# ProPrj_sx1262_125cm_v0_2_2026-07-31.net
KiCad netlist of a schematic drawn in EasyEDA Pro
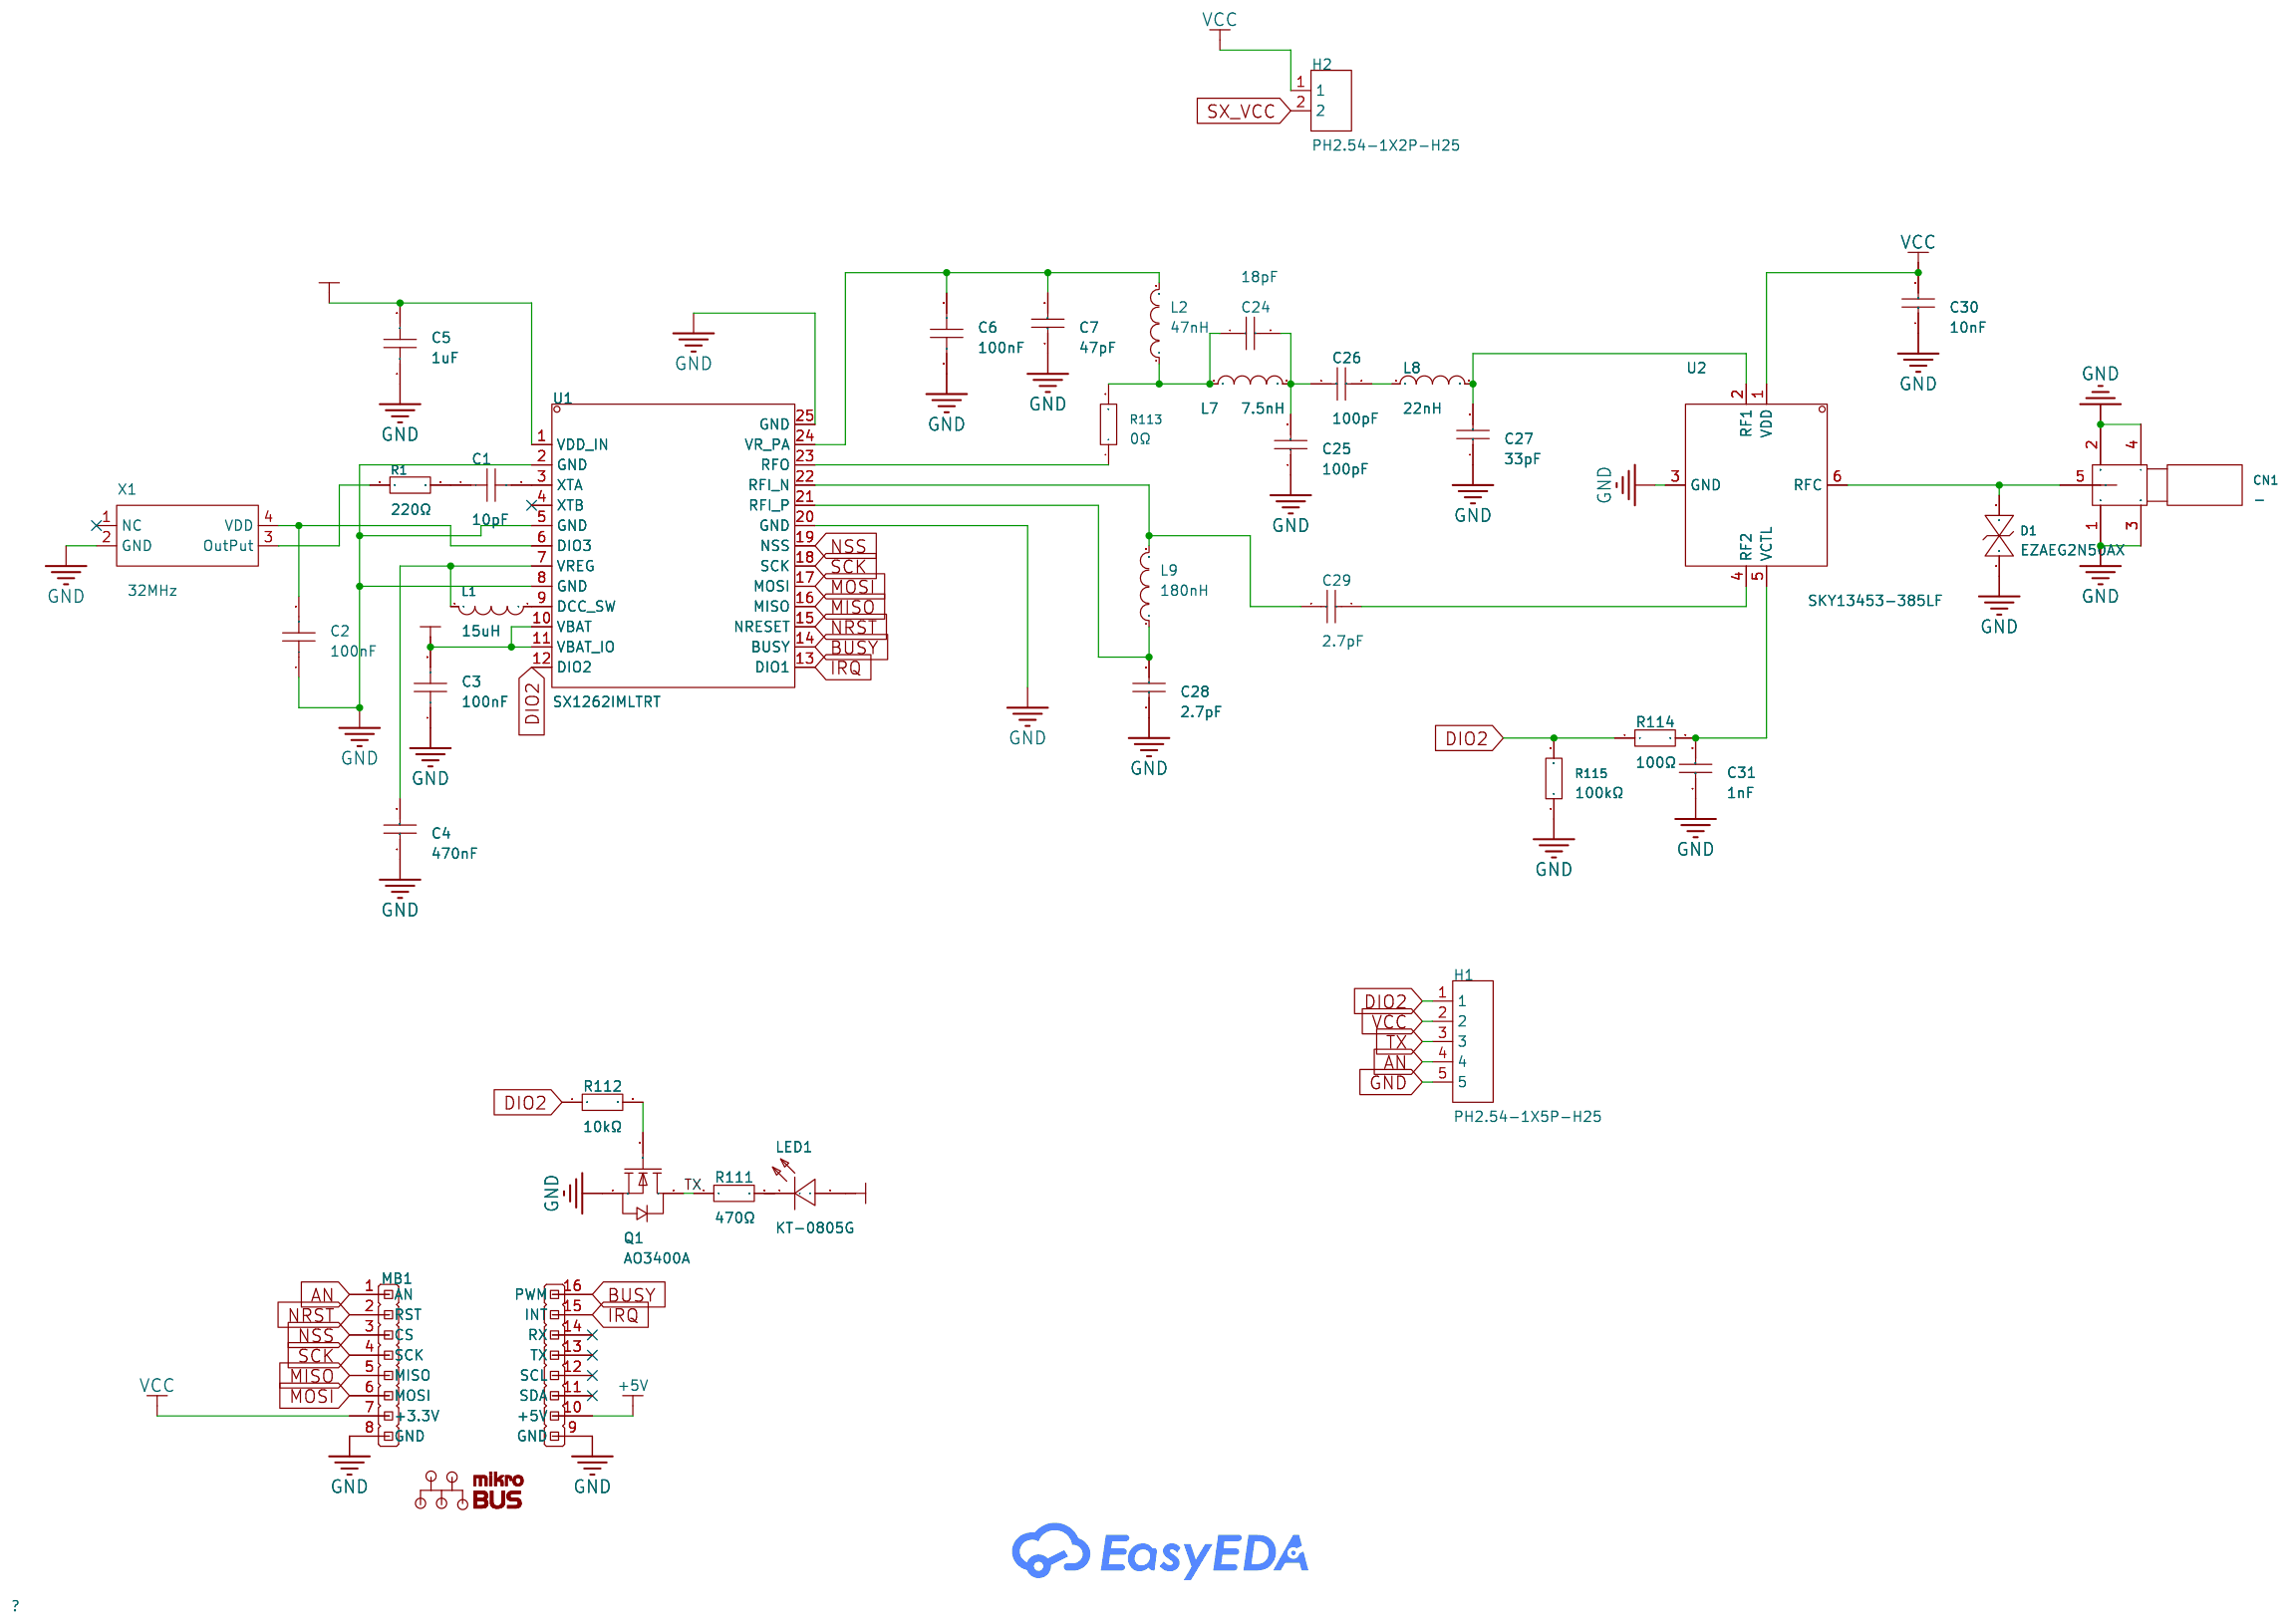
[diagram p0: schematic sheet]

(export (version "E")
  (design (tool "Eeschema 10.0.6"))
  (components
    (comp (ref "C1")
      (value "10pF")
      (footprint "easyedapro:C0402")
      (description "Capacitance:10pF Tolerance:±5% Tolerance:±5% Voltage Rating:50V Temperature Coefficient:C0G")
      (fields
        (field (name "Manufacturer Part") "CL05C100JB5NNNC")
        (field (name "Manufacturer") "SAMSUNG(三星)")
      )
      (libsource (lib "easyedapro") (part "CL05C100JB5NNNC"))
    )
    (comp (ref "C2")
      (value "100nF")
      (footprint "easyedapro:C0402")
      (description "Capacitance:100nF Tolerance:±10% Tolerance:±10% Voltage Rating:16V Temperature Coefficient:X7R")
      (fields
        (field (name "Manufacturer Part") "CL05B104KO5NNNC")
        (field (name "Manufacturer") "SAMSUNG(三星)")
      )
      (libsource (lib "easyedapro") (part "CL05B104KO5NNNC"))
    )
    (comp (ref "C3")
      (value "100nF")
      (footprint "easyedapro:C0402")
      (description "Capacitance:100nF Tolerance:±10% Tolerance:±10% Voltage Rating:16V Temperature Coefficient:X7R")
      (fields
        (field (name "Manufacturer Part") "CL05B104KO5NNNC")
        (field (name "Manufacturer") "SAMSUNG(三星)")
      )
      (libsource (lib "easyedapro") (part "CL05B104KO5NNNC"))
    )
    (comp (ref "C4")
      (value "470nF")
      (footprint "easyedapro:C0603")
      (description "Capacitance:470nF Tolerance:±10% Tolerance:±10% Voltage Rating:25V Temperature Coefficient:X7R")
      (fields
        (field (name "Manufacturer Part") "CL10B474KA8NNNC")
        (field (name "Manufacturer") "SAMSUNG(三星)")
      )
      (libsource (lib "easyedapro") (part "CL10B474KA8NNNC"))
    )
    (comp (ref "C5")
      (value "1uF")
      (footprint "easyedapro:C0402")
      (description "Capacitance:1uF Tolerance:±10% Tolerance:±10% Voltage Rating:25V Temperature Coefficient:X5R")
      (fields
        (field (name "Manufacturer Part") "CL05A105KA5NQNC")
        (field (name "Manufacturer") "SAMSUNG(三星)")
      )
      (libsource (lib "easyedapro") (part "CL05A105KA5NQNC"))
    )
    (comp (ref "C6")
      (value "100nF")
      (footprint "easyedapro:C0402")
      (description "Capacitance:100nF Tolerance:±10% Tolerance:±10% Voltage Rating:16V Temperature Coefficient:X7R")
      (fields
        (field (name "Manufacturer Part") "CL05B104KO5NNNC")
        (field (name "Manufacturer") "SAMSUNG(三星)")
      )
      (libsource (lib "easyedapro") (part "CL05B104KO5NNNC"))
    )
    (comp (ref "C7")
      (value "47pF")
      (footprint "easyedapro:C0402")
      (description "Capacitance:47pF Tolerance:±5% Tolerance:±5% Voltage Rating:50V Temperature Coefficient:C0G")
      (fields (field (name "Manufacturer Part") "0402CG470J500NT") (field (name "Manufacturer") "FH(风华)"))
      (libsource (lib "easyedapro") (part "0402CG470J500NT"))
    )
    (comp (ref "C24")
      (value "18pF")
      (footprint "easyedapro:C0402")
      (description "Capacitance:18pF Tolerance:±5% Tolerance:±5% Voltage Rating:50V Temperature Coefficient:C0G")
      (fields (field (name "Manufacturer Part") "0402CG180J500NT") (field (name "Manufacturer") "FH(风华)"))
      (libsource (lib "easyedapro") (part "0402CG330J500NT"))
    )
    (comp (ref "C25")
      (value "100pF")
      (footprint "easyedapro:C0402")
      (description "Capacitance:100pF Tolerance:±5% Tolerance:±5% Voltage Rating:50V Temperature Coefficient:C0G")
      (fields (field (name "Manufacturer Part") "0402CG101J500NT") (field (name "Manufacturer") "FH(风华)"))
      (libsource (lib "easyedapro") (part "GRM1555C1H8R2CA01D"))
    )
    (comp (ref "C26")
      (value "100pF")
      (footprint "easyedapro:C0402")
      (description "Capacitance:100pF Tolerance:±5% Tolerance:±5% Voltage Rating:50V Temperature Coefficient:C0G")
      (fields (field (name "Manufacturer Part") "0402CG101J500NT") (field (name "Manufacturer") "FH(风华)"))
      (libsource (lib "easyedapro") (part "0402CG4R7C500NT"))
    )
    (comp (ref "C27")
      (value "33pF")
      (footprint "easyedapro:C0402")
      (description "Capacitance:33pF Tolerance:±5% Tolerance:±5% Voltage Rating:50V Temperature Coefficient:C0G")
      (fields (field (name "Manufacturer Part") "0402CG330J500NT") (field (name "Manufacturer") "FH(风华)"))
      (libsource (lib "easyedapro") (part "0402CG120J500NT"))
    )
    (comp (ref "C28")
      (value "2.7pF")
      (footprint "easyedapro:C0402")
      (description "Capacitance:2.7pF Voltage Rating:50V Temperature Coefficient:C0G")
      (fields (field (name "Manufacturer Part") "0402CG2R7C500NT") (field (name "Manufacturer") "FH(风华)"))
      (libsource (lib "easyedapro") (part "0402CG180J500NT"))
    )
    (comp (ref "C29")
      (value "2.7pF")
      (footprint "easyedapro:C0402")
      (description "Capacitance:2.7pF Voltage Rating:50V Temperature Coefficient:C0G")
      (fields (field (name "Manufacturer Part") "0402CG2R7C500NT") (field (name "Manufacturer") "FH(风华)"))
      (libsource (lib "easyedapro") (part "0402CG180J500NT"))
    )
    (comp (ref "C30")
      (value "10nF")
      (footprint "easyedapro:C0402")
      (description "Capacitance:10nF Tolerance:±10% Tolerance:±10% Voltage Rating:50V Temperature Coefficient:X7R")
      (fields
        (field (name "Manufacturer Part") "CL05B103KB5NNNC")
        (field (name "Manufacturer") "SAMSUNG(三星)")
      )
      (libsource (lib "easyedapro") (part "0402B102K500NT"))
    )
    (comp (ref "C31")
      (value "1nF")
      (footprint "easyedapro:C0402")
      (description "Capacitance:1nF Tolerance:±10% Tolerance:±10% Voltage Rating:50V Temperature Coefficient:X7R")
      (fields (field (name "Manufacturer Part") "0402B102K500NT") (field (name "Manufacturer") "FH(风华)"))
      (libsource (lib "easyedapro") (part "0402B102K500NT"))
    )
    (comp (ref "CN1")
      (value "-")
      (footprint "easyedapro:CONN-SMD_KH-SMA-KE8-G")
      (fields (field (name "Manufacturer Part") "KH-SMA-KE8-G") (field (name "Manufacturer") "kinghelm(金航标)"))
      (libsource (lib "easyedapro") (part "KH-SMA-KE8-G"))
    )
    (comp (ref "D1")
      (value "EZAEG2N50AX")
      (footprint "easyedapro:D0402-BI")
      (fields (field (name "Manufacturer") "PANASONIC(松下)"))
      (libsource (lib "easyedapro") (part "EZAEG2N50AX"))
    )
    (comp (ref "H1")
      (value "PH2.54-1X5P-H25")
      (footprint "easyedapro:HDR-TH_5P-P2.54-V-M-3")
      (fields (field (name "Manufacturer") "JXTCONN(聚兴泰)"))
      (libsource (lib "easyedapro") (part "PH2.54-1X5P-H25"))
    )
    (comp (ref "H2")
      (value "PH2.54-1X2P-H25")
      (footprint "easyedapro:HDR-TH_2P-P2.54-V-M-4")
      (fields (field (name "Manufacturer") "JXTCONN(聚兴泰)"))
      (libsource (lib "easyedapro") (part "PH2.54-1X2P-H25"))
    )
    (comp (ref "L1")
      (value "15uH")
      (footprint "easyedapro:L0805")
      (fields (field (name "Manufacturer Part") "MLZ2012M150WT000") (field (name "Manufacturer") "TDK"))
      (libsource (lib "easyedapro") (part "MLZ2012M150WT000"))
    )
    (comp (ref "L2")
      (value "47nH")
      (footprint "easyedapro:IND-SMD_L1.2-W0.6-1")
      (fields
        (field (name "Manufacturer Part") "SCW1005C47NJST")
        (field (name "Manufacturer") "Sunltech(顺磁)")
      )
      (libsource (lib "easyedapro") (part "SCW1005C47NJST"))
    )
    (comp (ref "L7")
      (value "7.5nH")
      (footprint "easyedapro:IND-SMD_L1.2-W0.7")
      (fields (field (name "Manufacturer Part") "LQG15HS7N5J02D") (field (name "Manufacturer") "muRata(村田)"))
      (libsource (lib "easyedapro") (part "AHW1005C-15NJTF"))
    )
    (comp (ref "L8")
      (value "22nH")
      (footprint "easyedapro:IND-SMD_L1.2-W0.7")
      (fields
        (field (name "Manufacturer Part") "SCW1005C22NJST")
        (field (name "Manufacturer") "Sunltech(顺磁)")
      )
      (libsource (lib "easyedapro") (part "AHW1005C-27NJTF"))
    )
    (comp (ref "L9")
      (value "180nH")
      (footprint "easyedapro:IND-SMD_L1.2-W0.6-1")
      (fields (field (name "Manufacturer Part") "MLG1005SR18JTD25") (field (name "Manufacturer") "TDK"))
      (libsource (lib "easyedapro") (part "SCW1005C68NJST"))
    )
    (comp (ref "LED1")
      (value "KT-0805G")
      (footprint "easyedapro:LED0805-R-RD")
      (fields (field (name "Manufacturer") "KENTO"))
      (libsource (lib "easyedapro") (part "0805G (Green)"))
    )
    (comp (ref "MB1")
      (value "~")
      (footprint "easyedapro:mikroBUS add-on Board")
      (description "ClickBoard")
      (libsource (lib "easyedapro") (part "mikroBUS"))
    )
    (comp (ref "Q1")
      (value "AO3400A")
      (footprint "easyedapro:SOT-23-3_L2.9-W1.3-P1.90-LS2.4-BR")
      (fields (field (name "Manufacturer") "AOS"))
      (libsource (lib "easyedapro") (part "AO3400A"))
    )
    (comp (ref "R1")
      (value "220Ω")
      (footprint "easyedapro:R0402")
      (fields
        (field (name "Manufacturer Part") "0402WGF2200TCE")
        (field (name "Manufacturer") "UNI-ROYAL(厚声)")
      )
      (libsource (lib "easyedapro") (part "0402WGF2200TCE"))
    )
    (comp (ref "R111")
      (value "470Ω")
      (footprint "easyedapro:R0402")
      (fields
        (field (name "Manufacturer Part") "0402WGF4700TCE")
        (field (name "Manufacturer") "UNI-ROYAL(厚声)")
      )
      (libsource (lib "easyedapro") (part "0402WGF2200TCE"))
    )
    (comp (ref "R112")
      (value "10kΩ")
      (footprint "easyedapro:R0402")
      (fields
        (field (name "Manufacturer Part") "0402WGF1002TCE")
        (field (name "Manufacturer") "UNI-ROYAL(厚声)")
      )
      (libsource (lib "easyedapro") (part "0402WGF1002TCE"))
    )
    (comp (ref "R113")
      (value "0Ω")
      (footprint "easyedapro:R0402")
      (fields
        (field (name "Manufacturer Part") "0402WGF0000TCE")
        (field (name "Manufacturer") "UNI-ROYAL(厚声)")
      )
      (libsource (lib "easyedapro") (part "0402WGF0000TCE"))
    )
    (comp (ref "R114")
      (value "100Ω")
      (footprint "easyedapro:R0402")
      (fields
        (field (name "Manufacturer Part") "0402WGF1000TCE")
        (field (name "Manufacturer") "UNI-ROYAL(厚声)")
      )
      (libsource (lib "easyedapro") (part "0402WGF1000TCE"))
    )
    (comp (ref "R115")
      (value "100kΩ")
      (footprint "easyedapro:R0402")
      (fields
        (field (name "Manufacturer Part") "0402WGF1003TCE")
        (field (name "Manufacturer") "UNI-ROYAL(厚声)")
      )
      (libsource (lib "easyedapro") (part "0402WGF1003TCE"))
    )
    (comp (ref "U1")
      (value "SX1262IMLTRT")
      (footprint "easyedapro:QFN-24_L4.0-W4.0-P0.50-BL-EP2.6")
      (fields (field (name "Manufacturer") "SEMTECH"))
      (libsource (lib "easyedapro") (part "SX1262IMLTRT"))
    )
    (comp (ref "U2")
      (value "SKY13453-385LF")
      (footprint "easyedapro:QFN-6_L1.0-W1.0-P0.50-LS1.0-BL")
      (fields (field (name "Manufacturer") "SKYWORKS"))
      (libsource (lib "easyedapro") (part "SKY13453-385LF"))
    )
    (comp (ref "X1")
      (value "32MHz")
      (footprint "easyedapro:OSC-SMD_4P-L2.0-W1.6-BL_1")
      (fields
        (field (name "Manufacturer Part") "OW7EL89CANUXK7YLC-32M")
        (field (name "Manufacturer") "YXC(扬兴晶振)")
      )
      (libsource (lib "easyedapro") (part "OW7EL89CANUXK7YLC-32M"))
    )
  )
  (nets
    (net (code "1") (name "+5V") (class "Default")
      (node (ref "MB1") (pin "10") (pinfunction "+5V_10") (pintype "input"))
    )
    (net (code "2") (name "AN") (class "Default")
      (node (ref "H1") (pin "4") (pinfunction "4_4") (pintype "unspecified"))
      (node (ref "MB1") (pin "1") (pinfunction "AN_1") (pintype "input"))
    )
    (net (code "3") (name "BUSY") (class "Default")
      (node (ref "MB1") (pin "16") (pinfunction "PWM_16") (pintype "input"))
      (node (ref "U1") (pin "14") (pinfunction "BUSY_14") (pintype "unspecified"))
    )
    (net (code "4") (name "DIO2") (class "Default")
      (node (ref "H1") (pin "1") (pinfunction "1_1") (pintype "unspecified"))
      (node (ref "R112") (pin "1") (pinfunction "1_1") (pintype "input"))
      (node (ref "R114") (pin "1") (pinfunction "1_1") (pintype "input"))
      (node (ref "R115") (pin "2") (pinfunction "2_2") (pintype "input"))
      (node (ref "U1") (pin "12") (pinfunction "DIO2_12") (pintype "unspecified"))
    )
    (net (code "5") (name "GND") (class "Default")
      (node (ref "C2") (pin "1") (pinfunction "1_1") (pintype "unspecified"))
      (node (ref "C25") (pin "1") (pinfunction "1_1") (pintype "input"))
      (node (ref "C27") (pin "1") (pinfunction "1_1") (pintype "input"))
      (node (ref "C28") (pin "1") (pinfunction "1_1") (pintype "input"))
      (node (ref "C3") (pin "1") (pinfunction "1_1") (pintype "unspecified"))
      (node (ref "C30") (pin "1") (pinfunction "1_1") (pintype "input"))
      (node (ref "C31") (pin "1") (pinfunction "1_1") (pintype "input"))
      (node (ref "C4") (pin "1") (pinfunction "1_1") (pintype "input"))
      (node (ref "C5") (pin "1") (pinfunction "1_1") (pintype "unspecified"))
      (node (ref "C6") (pin "1") (pinfunction "1_1") (pintype "unspecified"))
      (node (ref "C7") (pin "1") (pinfunction "1_1") (pintype "input"))
      (node (ref "CN1") (pin "1") (pinfunction "1_1") (pintype "unspecified"))
      (node (ref "CN1") (pin "2") (pinfunction "2_2") (pintype "unspecified"))
      (node (ref "CN1") (pin "3") (pinfunction "3_3") (pintype "unspecified"))
      (node (ref "CN1") (pin "4") (pinfunction "4_4") (pintype "unspecified"))
      (node (ref "D1") (pin "1") (pinfunction "1_1") (pintype "input"))
      (node (ref "H1") (pin "5") (pinfunction "5_5") (pintype "unspecified"))
      (node (ref "MB1") (pin "8") (pinfunction "GND_8") (pintype "input"))
      (node (ref "MB1") (pin "9") (pinfunction "GND_9") (pintype "input"))
      (node (ref "Q1") (pin "2") (pinfunction "S_2") (pintype "unspecified"))
      (node (ref "R115") (pin "1") (pinfunction "1_1") (pintype "input"))
      (node (ref "U1") (pin "2") (pinfunction "GND_2") (pintype "unspecified"))
      (node (ref "U1") (pin "20") (pinfunction "GND_20") (pintype "unspecified"))
      (node (ref "U1") (pin "25") (pinfunction "GND_25") (pintype "unspecified"))
      (node (ref "U1") (pin "5") (pinfunction "GND_5") (pintype "unspecified"))
      (node (ref "U1") (pin "8") (pinfunction "GND_8") (pintype "unspecified"))
      (node (ref "U2") (pin "3") (pinfunction "GND_3") (pintype "unspecified"))
      (node (ref "X1") (pin "2") (pinfunction "GND_2") (pintype "unspecified"))
    )
    (net (code "6") (name "IRQ") (class "Default")
      (node (ref "MB1") (pin "15") (pinfunction "INT_15") (pintype "input"))
      (node (ref "U1") (pin "13") (pinfunction "DIO1_13") (pintype "unspecified"))
    )
    (net (code "7") (name "MISO") (class "Default")
      (node (ref "MB1") (pin "5") (pinfunction "MISO_5") (pintype "input"))
      (node (ref "U1") (pin "16") (pinfunction "MISO_16") (pintype "unspecified"))
    )
    (net (code "8") (name "MOSI") (class "Default")
      (node (ref "MB1") (pin "6") (pinfunction "MOSI_6") (pintype "input"))
      (node (ref "U1") (pin "17") (pinfunction "MOSI_17") (pintype "unspecified"))
    )
    (net (code "9") (name "NRST") (class "Default")
      (node (ref "MB1") (pin "2") (pinfunction "RST_2") (pintype "input"))
      (node (ref "U1") (pin "15") (pinfunction "NRESET_15") (pintype "unspecified"))
    )
    (net (code "10") (name "NSS") (class "Default")
      (node (ref "MB1") (pin "3") (pinfunction "CS_3") (pintype "input"))
      (node (ref "U1") (pin "19") (pinfunction "NSS_19") (pintype "unspecified"))
    )
    (net (code "11") (name "Net-(C1-Pad1)") (class "Default")
      (node (ref "C1") (pin "1") (pinfunction "1_1") (pintype "unspecified"))
      (node (ref "R1") (pin "2") (pinfunction "2_2") (pintype "input"))
    )
    (net (code "12") (name "Net-(C24-Pad1)") (class "Default")
      (node (ref "C24") (pin "1") (pinfunction "1_1") (pintype "input"))
      (node (ref "L2") (pin "1") (pinfunction "1_1") (pintype "unspecified"))
      (node (ref "L7") (pin "1") (pinfunction "1_1") (pintype "unspecified"))
      (node (ref "R113") (pin "2") (pinfunction "2_2") (pintype "input"))
    )
    (net (code "13") (name "Net-(C24-Pad2)") (class "Default")
      (node (ref "C24") (pin "2") (pinfunction "2_2") (pintype "input"))
      (node (ref "C25") (pin "2") (pinfunction "2_2") (pintype "input"))
      (node (ref "C26") (pin "1") (pinfunction "1_1") (pintype "input"))
      (node (ref "L7") (pin "2") (pinfunction "2_2") (pintype "unspecified"))
    )
    (net (code "14") (name "Net-(C26-Pad2)") (class "Default")
      (node (ref "C26") (pin "2") (pinfunction "2_2") (pintype "input"))
      (node (ref "L8") (pin "1") (pinfunction "1_1") (pintype "unspecified"))
    )
    (net (code "15") (name "Net-(LED1-K)") (class "Default")
      (node (ref "LED1") (pin "2") (pinfunction "K_2") (pintype "unspecified"))
      (node (ref "R111") (pin "2") (pinfunction "2_2") (pintype "input"))
    )
    (net (code "16") (name "Net-(Q1-G)") (class "Default")
      (node (ref "Q1") (pin "1") (pinfunction "G_1") (pintype "unspecified"))
      (node (ref "R112") (pin "2") (pinfunction "2_2") (pintype "input"))
    )
    (net (code "17") (name "Net-(U1-DCC_SW)") (class "Default")
      (node (ref "L1") (pin "1") (pinfunction "1_1") (pintype "input"))
      (node (ref "U1") (pin "9") (pinfunction "DCC_SW_9") (pintype "unspecified"))
    )
    (net (code "18") (name "Net-(U1-DIO3)") (class "Default")
      (node (ref "C2") (pin "2") (pinfunction "2_2") (pintype "unspecified"))
      (node (ref "U1") (pin "6") (pinfunction "DIO3_6") (pintype "unspecified"))
      (node (ref "X1") (pin "4") (pinfunction "VDD_4") (pintype "unspecified"))
    )
    (net (code "19") (name "Net-(U1-RFI_N)") (class "Default")
      (node (ref "C29") (pin "2") (pinfunction "2_2") (pintype "input"))
      (node (ref "L9") (pin "2") (pinfunction "2_2") (pintype "unspecified"))
      (node (ref "U1") (pin "22") (pinfunction "RFI_N_22") (pintype "unspecified"))
    )
    (net (code "20") (name "Net-(U1-RFI_P)") (class "Default")
      (node (ref "C28") (pin "2") (pinfunction "2_2") (pintype "input"))
      (node (ref "L9") (pin "1") (pinfunction "1_1") (pintype "unspecified"))
      (node (ref "U1") (pin "21") (pinfunction "RFI_P_21") (pintype "unspecified"))
    )
    (net (code "21") (name "Net-(U1-RFO)") (class "Default")
      (node (ref "R113") (pin "1") (pinfunction "1_1") (pintype "input"))
      (node (ref "U1") (pin "23") (pinfunction "RFO_23") (pintype "unspecified"))
    )
    (net (code "22") (name "Net-(U1-VREG)") (class "Default")
      (node (ref "C4") (pin "2") (pinfunction "2_2") (pintype "input"))
      (node (ref "L1") (pin "2") (pinfunction "2_2") (pintype "input"))
      (node (ref "U1") (pin "7") (pinfunction "VREG_7") (pintype "unspecified"))
    )
    (net (code "23") (name "Net-(U1-VR_PA)") (class "Default")
      (node (ref "C6") (pin "2") (pinfunction "2_2") (pintype "unspecified"))
      (node (ref "C7") (pin "2") (pinfunction "2_2") (pintype "input"))
      (node (ref "L2") (pin "2") (pinfunction "2_2") (pintype "unspecified"))
      (node (ref "U1") (pin "24") (pinfunction "VR_PA_24") (pintype "unspecified"))
    )
    (net (code "24") (name "Net-(U1-XTA)") (class "Default")
      (node (ref "C1") (pin "2") (pinfunction "2_2") (pintype "unspecified"))
      (node (ref "U1") (pin "3") (pinfunction "XTA_3") (pintype "unspecified"))
    )
    (net (code "25") (name "Net-(U2-RF1)") (class "Default")
      (node (ref "C27") (pin "2") (pinfunction "2_2") (pintype "input"))
      (node (ref "L8") (pin "2") (pinfunction "2_2") (pintype "unspecified"))
      (node (ref "U2") (pin "2") (pinfunction "RF1_2") (pintype "unspecified"))
    )
    (net (code "26") (name "Net-(U2-RF2)") (class "Default")
      (node (ref "C29") (pin "1") (pinfunction "1_1") (pintype "input"))
      (node (ref "U2") (pin "4") (pinfunction "RF2_4") (pintype "unspecified"))
    )
    (net (code "27") (name "Net-(U2-RFC)") (class "Default")
      (node (ref "CN1") (pin "5") (pinfunction "5_5") (pintype "unspecified"))
      (node (ref "D1") (pin "2") (pinfunction "2_2") (pintype "input"))
      (node (ref "U2") (pin "6") (pinfunction "RFC_6") (pintype "unspecified"))
    )
    (net (code "28") (name "Net-(U2-VCTL)") (class "Default")
      (node (ref "C31") (pin "2") (pinfunction "2_2") (pintype "input"))
      (node (ref "R114") (pin "2") (pinfunction "2_2") (pintype "input"))
      (node (ref "U2") (pin "5") (pinfunction "VCTL_5") (pintype "unspecified"))
    )
    (net (code "29") (name "Net-(X1-OutPut)") (class "Default")
      (node (ref "R1") (pin "1") (pinfunction "1_1") (pintype "input"))
      (node (ref "X1") (pin "3") (pinfunction "OutPut_3") (pintype "unspecified"))
    )
    (net (code "30") (name "SCK") (class "Default")
      (node (ref "MB1") (pin "4") (pinfunction "SCK_4") (pintype "input"))
      (node (ref "U1") (pin "18") (pinfunction "SCK_18") (pintype "unspecified"))
    )
    (net (code "31") (name "SX_VCC") (class "Default")
      (node (ref "C3") (pin "2") (pinfunction "2_2") (pintype "unspecified"))
      (node (ref "C5") (pin "2") (pinfunction "2_2") (pintype "unspecified"))
      (node (ref "H2") (pin "2") (pinfunction "2_2") (pintype "unspecified"))
      (node (ref "U1") (pin "1") (pinfunction "VDD_IN_1") (pintype "unspecified"))
      (node (ref "U1") (pin "10") (pinfunction "VBAT_10") (pintype "unspecified"))
      (node (ref "U1") (pin "11") (pinfunction "VBAT_IO_11") (pintype "unspecified"))
    )
    (net (code "32") (name "TX") (class "Default")
      (node (ref "H1") (pin "3") (pinfunction "3_3") (pintype "unspecified"))
      (node (ref "Q1") (pin "3") (pinfunction "D_3") (pintype "unspecified"))
      (node (ref "R111") (pin "1") (pinfunction "1_1") (pintype "input"))
    )
    (net (code "33") (name "VCC") (class "Default")
      (node (ref "C30") (pin "2") (pinfunction "2_2") (pintype "input"))
      (node (ref "H1") (pin "2") (pinfunction "2_2") (pintype "unspecified"))
      (node (ref "H2") (pin "1") (pinfunction "1_1") (pintype "unspecified"))
      (node (ref "LED1") (pin "1") (pinfunction "A_1") (pintype "unspecified"))
      (node (ref "MB1") (pin "7") (pinfunction "+3.3V_7") (pintype "input"))
      (node (ref "U2") (pin "1") (pinfunction "VDD_1") (pintype "unspecified"))
    )
    (net (code "34") (name "unconnected-(MB1-RX-Pad14)") (class "Default")
      (node (ref "MB1") (pin "14") (pinfunction "RX_14") (pintype "input+no_connect"))
    )
    (net (code "35") (name "unconnected-(MB1-SCL-Pad12)") (class "Default")
      (node (ref "MB1") (pin "12") (pinfunction "SCL_12") (pintype "input+no_connect"))
    )
    (net (code "36") (name "unconnected-(MB1-SDA-Pad11)") (class "Default")
      (node (ref "MB1") (pin "11") (pinfunction "SDA_11") (pintype "input+no_connect"))
    )
    (net (code "37") (name "unconnected-(MB1-TX-Pad13)") (class "Default")
      (node (ref "MB1") (pin "13") (pinfunction "TX_13") (pintype "input+no_connect"))
    )
    (net (code "38") (name "unconnected-(U1-XTB-Pad4)") (class "Default")
      (node (ref "U1") (pin "4") (pinfunction "XTB_4") (pintype "unspecified+no_connect"))
    )
    (net (code "39") (name "unconnected-(X1-NC-Pad1)") (class "Default")
      (node (ref "X1") (pin "1") (pinfunction "NC_1") (pintype "unspecified+no_connect"))
    )
  )
)
